# ArduinoFanController.net
KiCad netlist of a schematic drawn in Altium Designer
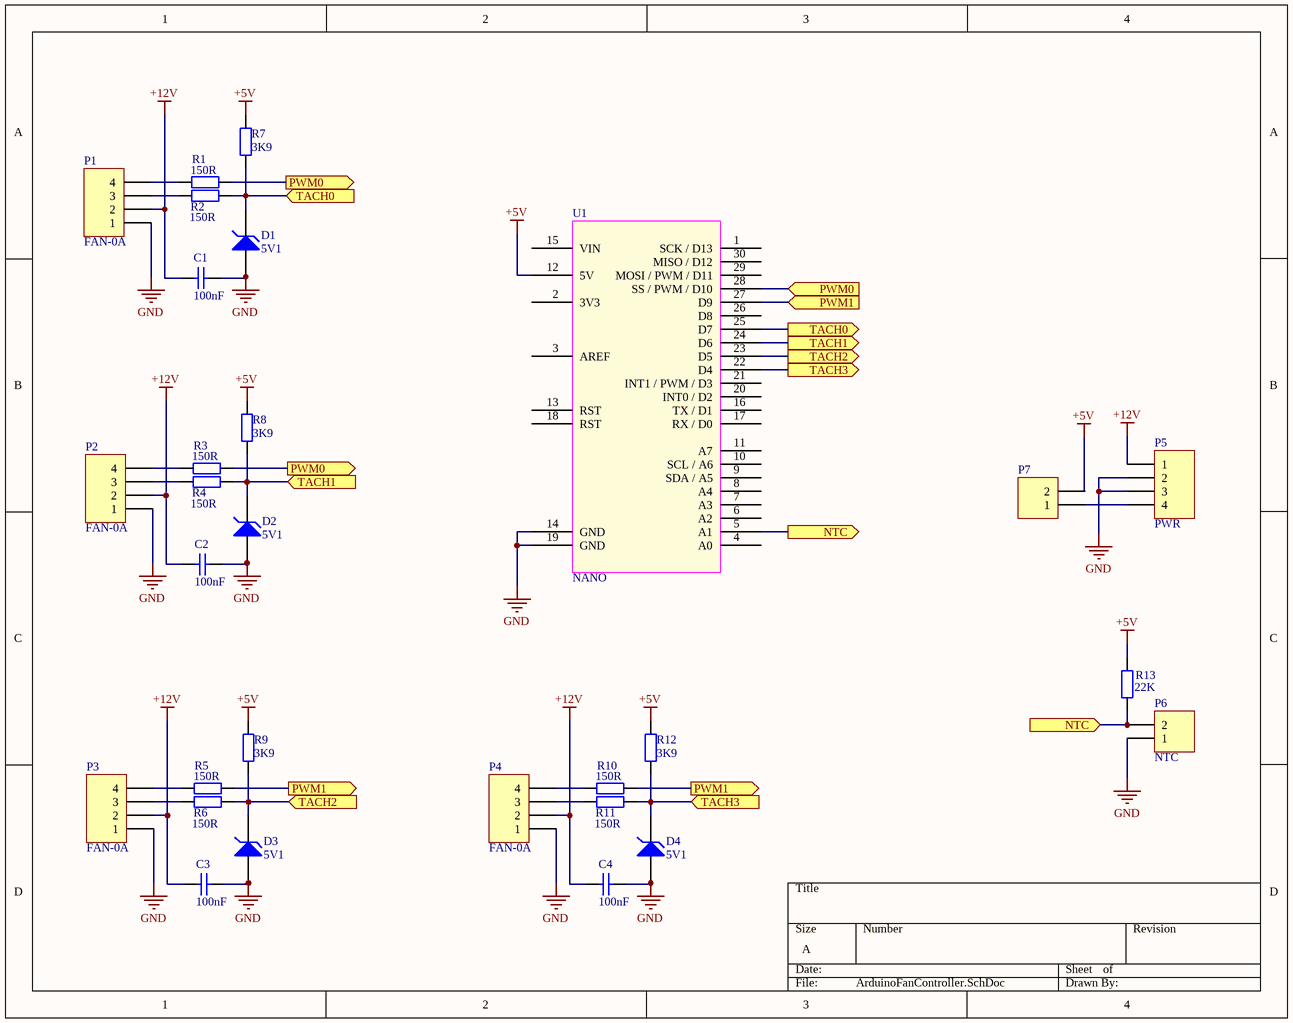
[diagram p0: ArduinoFanController.SchDoc]

(export (version "E")
  (design (tool "Eeschema 10.0.6"))
  (components
    (comp (ref "C1")
      (value "100nF")
      (footprint "CAP200")
      (description "Capacitor")
      (libsource (lib "RBM") (part "Cap np"))
    )
    (comp (ref "C2")
      (value "100nF")
      (footprint "CAP200")
      (description "Capacitor")
      (libsource (lib "RBM") (part "Cap np"))
    )
    (comp (ref "C3")
      (value "100nF")
      (footprint "CAP200")
      (description "Capacitor")
      (libsource (lib "RBM") (part "Cap np"))
    )
    (comp (ref "C4")
      (value "100nF")
      (footprint "CAP200")
      (description "Capacitor")
      (libsource (lib "RBM") (part "Cap np"))
    )
    (comp (ref "D1")
      (value "5V1")
      (footprint "DIODE-0.4")
      (description "Zener Diode")
      (fields (field (name "PUBLISHER") "Altium Limited"))
      (libsource (lib "Miscellaneous Devices") (part "D Zener"))
    )
    (comp (ref "D2")
      (value "5V1")
      (footprint "DIODE-0.4")
      (description "Zener Diode")
      (fields (field (name "PUBLISHER") "Altium Limited"))
      (libsource (lib "Miscellaneous Devices") (part "D Zener"))
    )
    (comp (ref "D3")
      (value "5V1")
      (footprint "DIODE-0.4")
      (description "Zener Diode")
      (fields (field (name "PUBLISHER") "Altium Limited"))
      (libsource (lib "Miscellaneous Devices") (part "D Zener"))
    )
    (comp (ref "D4")
      (value "5V1")
      (footprint "DIODE-0.4")
      (description "Zener Diode")
      (fields (field (name "PUBLISHER") "Altium Limited"))
      (libsource (lib "Miscellaneous Devices") (part "D Zener"))
    )
    (comp (ref "P1")
      (value "FAN-0A")
      (footprint "HDR1X4")
      (description "Header, 4-Pin")
      (fields (field (name "PUBLISHER") "Altium Limited"))
      (libsource (lib "Miscellaneous Connectors") (part "Header 4"))
    )
    (comp (ref "P2")
      (value "FAN-0A")
      (footprint "HDR1X4")
      (description "Header, 4-Pin")
      (fields (field (name "PUBLISHER") "Altium Limited"))
      (libsource (lib "Miscellaneous Connectors") (part "Header 4"))
    )
    (comp (ref "P3")
      (value "FAN-0A")
      (footprint "HDR1X4")
      (description "Header, 4-Pin")
      (fields (field (name "PUBLISHER") "Altium Limited"))
      (libsource (lib "Miscellaneous Connectors") (part "Header 4"))
    )
    (comp (ref "P4")
      (value "FAN-0A")
      (footprint "HDR1X4")
      (description "Header, 4-Pin")
      (fields (field (name "PUBLISHER") "Altium Limited"))
      (libsource (lib "Miscellaneous Connectors") (part "Header 4"))
    )
    (comp (ref "P5")
      (value "PWR")
      (footprint "MOLEX4")
      (description "PC Molex connector, 4-Pin")
      (fields (field (name "PUBLISHER") "Altium Limited"))
      (libsource (lib "RBM") (part "Molex 4"))
    )
    (comp (ref "P6")
      (value "NTC")
      (footprint "HDR1X2")
      (description "Header, 2-Pin")
      (fields (field (name "PUBLISHER") "Altium Limited"))
      (libsource (lib "Miscellaneous Connectors") (part "Header 2"))
    )
    (comp (ref "P7")
      (value "Header 2")
      (footprint "HDR1X2")
      (description "Header, 2-Pin")
      (fields (field (name "PUBLISHER") "Altium Limited"))
      (libsource (lib "") (part "Header 2_1"))
    )
    (comp (ref "R1")
      (value "150R")
      (footprint "AXIAL-0.4")
      (description "Resistor")
      (fields (field (name "Comment") "Res2") (field (name "PUBLISHER") "Altium Limited"))
      (libsource (lib "") (part "Res2_1"))
    )
    (comp (ref "R2")
      (value "150R")
      (footprint "AXIAL-0.4")
      (description "Resistor")
      (fields (field (name "Comment") "Res2") (field (name "PUBLISHER") "Altium Limited"))
      (libsource (lib "") (part "Res2_1"))
    )
    (comp (ref "R3")
      (value "150R")
      (footprint "AXIAL-0.4")
      (description "Resistor")
      (fields (field (name "Comment") "Res2") (field (name "PUBLISHER") "Altium Limited"))
      (libsource (lib "") (part "Res2_1"))
    )
    (comp (ref "R4")
      (value "150R")
      (footprint "AXIAL-0.4")
      (description "Resistor")
      (fields (field (name "Comment") "Res2") (field (name "PUBLISHER") "Altium Limited"))
      (libsource (lib "") (part "Res2_1"))
    )
    (comp (ref "R5")
      (value "150R")
      (footprint "AXIAL-0.4")
      (description "Resistor")
      (fields (field (name "Comment") "Res2") (field (name "PUBLISHER") "Altium Limited"))
      (libsource (lib "") (part "Res2_1"))
    )
    (comp (ref "R6")
      (value "150R")
      (footprint "AXIAL-0.4")
      (description "Resistor")
      (fields (field (name "Comment") "Res2") (field (name "PUBLISHER") "Altium Limited"))
      (libsource (lib "") (part "Res2_1"))
    )
    (comp (ref "R7")
      (value "3K9")
      (footprint "AXIAL-0.4")
      (description "Resistor")
      (fields (field (name "Comment") "Res2") (field (name "PUBLISHER") "Altium Limited"))
      (libsource (lib "Miscellaneous Devices") (part "Res2"))
    )
    (comp (ref "R8")
      (value "3K9")
      (footprint "AXIAL-0.4")
      (description "Resistor")
      (fields (field (name "Comment") "Res2") (field (name "PUBLISHER") "Altium Limited"))
      (libsource (lib "Miscellaneous Devices") (part "Res2"))
    )
    (comp (ref "R9")
      (value "3K9")
      (footprint "AXIAL-0.4")
      (description "Resistor")
      (fields (field (name "Comment") "Res2") (field (name "PUBLISHER") "Altium Limited"))
      (libsource (lib "Miscellaneous Devices") (part "Res2"))
    )
    (comp (ref "R10")
      (value "150R")
      (footprint "AXIAL-0.4")
      (description "Resistor")
      (fields (field (name "Comment") "Res2") (field (name "PUBLISHER") "Altium Limited"))
      (libsource (lib "") (part "Res2_1"))
    )
    (comp (ref "R11")
      (value "150R")
      (footprint "AXIAL-0.4")
      (description "Resistor")
      (fields (field (name "Comment") "Res2") (field (name "PUBLISHER") "Altium Limited"))
      (libsource (lib "") (part "Res2_1"))
    )
    (comp (ref "R12")
      (value "3K9")
      (footprint "AXIAL-0.4")
      (description "Resistor")
      (fields (field (name "Comment") "Res2") (field (name "PUBLISHER") "Altium Limited"))
      (libsource (lib "Miscellaneous Devices") (part "Res2"))
    )
    (comp (ref "R13")
      (value "22K")
      (footprint "AXIAL-0.4")
      (description "Resistor")
      (fields (field (name "Comment") "Res2") (field (name "PUBLISHER") "Altium Limited"))
      (libsource (lib "") (part "Res2_2"))
    )
    (comp (ref "U1")
      (value "NANO")
      (footprint "DIP30")
      (description "Arduino Nano")
      (libsource (lib "RBM") (part "Arduino Nano"))
    )
  )
  (nets
    (net (code "1") (name "+5V") (class "Default")
      (node (ref "P7") (pin "2") (pinfunction "2_2") (pintype "passive"))
      (node (ref "R12") (pin "2") (pinfunction "2_2") (pintype "passive"))
      (node (ref "R13") (pin "2") (pinfunction "2_2") (pintype "passive"))
      (node (ref "R7") (pin "2") (pinfunction "2_2") (pintype "passive"))
      (node (ref "R8") (pin "2") (pinfunction "2_2") (pintype "passive"))
      (node (ref "R9") (pin "2") (pinfunction "2_2") (pintype "passive"))
      (node (ref "U1") (pin "12") (pinfunction "5V_12") (pintype "passive"))
    )
    (net (code "2") (name "+12V") (class "Default")
      (node (ref "C1") (pin "1") (pinfunction "1_1") (pintype "passive"))
      (node (ref "C2") (pin "1") (pinfunction "1_1") (pintype "passive"))
      (node (ref "C3") (pin "1") (pinfunction "1_1") (pintype "passive"))
      (node (ref "C4") (pin "1") (pinfunction "1_1") (pintype "passive"))
      (node (ref "P1") (pin "2") (pinfunction "2_2") (pintype "passive"))
      (node (ref "P2") (pin "2") (pinfunction "2_2") (pintype "passive"))
      (node (ref "P3") (pin "2") (pinfunction "2_2") (pintype "passive"))
      (node (ref "P4") (pin "2") (pinfunction "2_2") (pintype "passive"))
      (node (ref "P5") (pin "1") (pinfunction "1_1") (pintype "passive"))
    )
    (net (code "3") (name "/NTC") (class "Default")
      (node (ref "P6") (pin "2") (pinfunction "2_2") (pintype "passive"))
      (node (ref "R13") (pin "1") (pinfunction "1_1") (pintype "passive"))
      (node (ref "U1") (pin "5") (pinfunction "A1_5") (pintype "passive"))
    )
    (net (code "4") (name "/PWM0") (class "Default")
      (node (ref "R1") (pin "1") (pinfunction "1_1") (pintype "passive"))
      (node (ref "R3") (pin "1") (pinfunction "1_1") (pintype "passive"))
      (node (ref "U1") (pin "28") (pinfunction "SS_/_PWM_/_D10_28") (pintype "passive"))
    )
    (net (code "5") (name "/PWM1") (class "Default")
      (node (ref "R10") (pin "1") (pinfunction "1_1") (pintype "passive"))
      (node (ref "R5") (pin "1") (pinfunction "1_1") (pintype "passive"))
      (node (ref "U1") (pin "27") (pinfunction "D9_27") (pintype "passive"))
    )
    (net (code "6") (name "/TACH0") (class "Default")
      (node (ref "D1") (pin "2") (pinfunction "K_2") (pintype "passive"))
      (node (ref "R2") (pin "1") (pinfunction "1_1") (pintype "passive"))
      (node (ref "R7") (pin "1") (pinfunction "1_1") (pintype "passive"))
      (node (ref "U1") (pin "25") (pinfunction "D7_25") (pintype "passive"))
    )
    (net (code "7") (name "/TACH1") (class "Default")
      (node (ref "D2") (pin "2") (pinfunction "K_2") (pintype "passive"))
      (node (ref "R4") (pin "1") (pinfunction "1_1") (pintype "passive"))
      (node (ref "R8") (pin "1") (pinfunction "1_1") (pintype "passive"))
      (node (ref "U1") (pin "24") (pinfunction "D6_24") (pintype "passive"))
    )
    (net (code "8") (name "/TACH2") (class "Default")
      (node (ref "D3") (pin "2") (pinfunction "K_2") (pintype "passive"))
      (node (ref "R6") (pin "1") (pinfunction "1_1") (pintype "passive"))
      (node (ref "R9") (pin "1") (pinfunction "1_1") (pintype "passive"))
      (node (ref "U1") (pin "23") (pinfunction "D5_23") (pintype "passive"))
    )
    (net (code "9") (name "/TACH3") (class "Default")
      (node (ref "D4") (pin "2") (pinfunction "K_2") (pintype "passive"))
      (node (ref "R11") (pin "1") (pinfunction "1_1") (pintype "passive"))
      (node (ref "R12") (pin "1") (pinfunction "1_1") (pintype "passive"))
      (node (ref "U1") (pin "22") (pinfunction "D4_22") (pintype "passive"))
    )
    (net (code "10") (name "GND") (class "Default")
      (node (ref "C1") (pin "2") (pinfunction "2_2") (pintype "passive"))
      (node (ref "C2") (pin "2") (pinfunction "2_2") (pintype "passive"))
      (node (ref "C3") (pin "2") (pinfunction "2_2") (pintype "passive"))
      (node (ref "C4") (pin "2") (pinfunction "2_2") (pintype "passive"))
      (node (ref "D1") (pin "1") (pinfunction "A_1") (pintype "passive"))
      (node (ref "D2") (pin "1") (pinfunction "A_1") (pintype "passive"))
      (node (ref "D3") (pin "1") (pinfunction "A_1") (pintype "passive"))
      (node (ref "D4") (pin "1") (pinfunction "A_1") (pintype "passive"))
      (node (ref "P1") (pin "1") (pinfunction "1_1") (pintype "passive"))
      (node (ref "P2") (pin "1") (pinfunction "1_1") (pintype "passive"))
      (node (ref "P3") (pin "1") (pinfunction "1_1") (pintype "passive"))
      (node (ref "P4") (pin "1") (pinfunction "1_1") (pintype "passive"))
      (node (ref "P5") (pin "2") (pinfunction "2_2") (pintype "passive"))
      (node (ref "P5") (pin "3") (pinfunction "3_3") (pintype "passive"))
      (node (ref "P6") (pin "1") (pinfunction "1_1") (pintype "passive"))
      (node (ref "U1") (pin "14") (pinfunction "GND_14") (pintype "passive"))
      (node (ref "U1") (pin "19") (pinfunction "GND_19") (pintype "passive"))
    )
    (net (code "11") (name "Net-(P1-Pad3)") (class "Default")
      (node (ref "P1") (pin "3") (pinfunction "3_3") (pintype "passive"))
      (node (ref "R2") (pin "2") (pinfunction "2_2") (pintype "passive"))
    )
    (net (code "12") (name "Net-(P1-Pad4)") (class "Default")
      (node (ref "P1") (pin "4") (pinfunction "4_4") (pintype "passive"))
      (node (ref "R1") (pin "2") (pinfunction "2_2") (pintype "passive"))
    )
    (net (code "13") (name "Net-(P2-Pad3)") (class "Default")
      (node (ref "P2") (pin "3") (pinfunction "3_3") (pintype "passive"))
      (node (ref "R4") (pin "2") (pinfunction "2_2") (pintype "passive"))
    )
    (net (code "14") (name "Net-(P2-Pad4)") (class "Default")
      (node (ref "P2") (pin "4") (pinfunction "4_4") (pintype "passive"))
      (node (ref "R3") (pin "2") (pinfunction "2_2") (pintype "passive"))
    )
    (net (code "15") (name "Net-(P3-Pad3)") (class "Default")
      (node (ref "P3") (pin "3") (pinfunction "3_3") (pintype "passive"))
      (node (ref "R6") (pin "2") (pinfunction "2_2") (pintype "passive"))
    )
    (net (code "16") (name "Net-(P3-Pad4)") (class "Default")
      (node (ref "P3") (pin "4") (pinfunction "4_4") (pintype "passive"))
      (node (ref "R5") (pin "2") (pinfunction "2_2") (pintype "passive"))
    )
    (net (code "17") (name "Net-(P4-Pad3)") (class "Default")
      (node (ref "P4") (pin "3") (pinfunction "3_3") (pintype "passive"))
      (node (ref "R11") (pin "2") (pinfunction "2_2") (pintype "passive"))
    )
    (net (code "18") (name "Net-(P4-Pad4)") (class "Default")
      (node (ref "P4") (pin "4") (pinfunction "4_4") (pintype "passive"))
      (node (ref "R10") (pin "2") (pinfunction "2_2") (pintype "passive"))
    )
    (net (code "19") (name "Net-(P5-Pad4)") (class "Default")
      (node (ref "P5") (pin "4") (pinfunction "4_4") (pintype "passive"))
      (node (ref "P7") (pin "1") (pinfunction "1_1") (pintype "passive"))
    )
    (net (code "20") (name "unconnected-(U1-3V3-Pad2)") (class "Default")
      (node (ref "U1") (pin "2") (pinfunction "3V3_2") (pintype "passive"))
    )
    (net (code "21") (name "unconnected-(U1-A0-Pad4)") (class "Default")
      (node (ref "U1") (pin "4") (pinfunction "A0_4") (pintype "passive"))
    )
    (net (code "22") (name "unconnected-(U1-A2-Pad6)") (class "Default")
      (node (ref "U1") (pin "6") (pinfunction "A2_6") (pintype "passive"))
    )
    (net (code "23") (name "unconnected-(U1-A3-Pad7)") (class "Default")
      (node (ref "U1") (pin "7") (pinfunction "A3_7") (pintype "passive"))
    )
    (net (code "24") (name "unconnected-(U1-A4-Pad8)") (class "Default")
      (node (ref "U1") (pin "8") (pinfunction "A4_8") (pintype "passive"))
    )
    (net (code "25") (name "unconnected-(U1-A7-Pad11)") (class "Default")
      (node (ref "U1") (pin "11") (pinfunction "A7_11") (pintype "passive"))
    )
    (net (code "26") (name "unconnected-(U1-AREF-Pad3)") (class "Default")
      (node (ref "U1") (pin "3") (pinfunction "AREF_3") (pintype "passive"))
    )
    (net (code "27") (name "unconnected-(U1-D8-Pad26)") (class "Default")
      (node (ref "U1") (pin "26") (pinfunction "D8_26") (pintype "passive"))
    )
    (net (code "28") (name "unconnected-(U1-INT0_{slash}_D2-Pad20)") (class "Default")
      (node (ref "U1") (pin "20") (pinfunction "INT0_/_D2_20") (pintype "passive"))
    )
    (net (code "29") (name "unconnected-(U1-INT1_{slash}_PWM_{slash}_D3-Pad21)") (class "Default")
      (node (ref "U1") (pin "21") (pinfunction "INT1_/_PWM_/_D3_21") (pintype "passive"))
    )
    (net (code "30") (name "unconnected-(U1-MISO_{slash}_D12-Pad30)") (class "Default")
      (node (ref "U1") (pin "30") (pinfunction "MISO_/_D12_30") (pintype "passive"))
    )
    (net (code "31") (name "unconnected-(U1-MOSI_{slash}_PWM_{slash}_D11-Pad29)") (class "Default")
      (node (ref "U1") (pin "29") (pinfunction "MOSI_/_PWM_/_D11_29") (pintype "passive"))
    )
    (net (code "32") (name "unconnected-(U1-RST-Pad13)") (class "Default")
      (node (ref "U1") (pin "13") (pinfunction "RST_13") (pintype "passive"))
    )
    (net (code "33") (name "unconnected-(U1-RST-Pad18)") (class "Default")
      (node (ref "U1") (pin "18") (pinfunction "RST_18") (pintype "passive"))
    )
    (net (code "34") (name "unconnected-(U1-RX_{slash}_D0-Pad17)") (class "Default")
      (node (ref "U1") (pin "17") (pinfunction "RX_/_D0_17") (pintype "passive"))
    )
    (net (code "35") (name "unconnected-(U1-SCK_{slash}_D13-Pad1)") (class "Default")
      (node (ref "U1") (pin "1") (pinfunction "SCK_/_D13_1") (pintype "passive"))
    )
    (net (code "36") (name "unconnected-(U1-SCL_{slash}_A6-Pad10)") (class "Default")
      (node (ref "U1") (pin "10") (pinfunction "SCL_/_A6_10") (pintype "passive"))
    )
    (net (code "37") (name "unconnected-(U1-SDA_{slash}_A5-Pad9)") (class "Default")
      (node (ref "U1") (pin "9") (pinfunction "SDA_/_A5_9") (pintype "passive"))
    )
    (net (code "38") (name "unconnected-(U1-TX_{slash}_D1-Pad16)") (class "Default")
      (node (ref "U1") (pin "16") (pinfunction "TX_/_D1_16") (pintype "passive"))
    )
    (net (code "39") (name "unconnected-(U1-VIN-Pad15)") (class "Default")
      (node (ref "U1") (pin "15") (pinfunction "VIN_15") (pintype "passive"))
    )
  )
)
